# green.net
KiCad netlist of a schematic drawn in Altium Designer
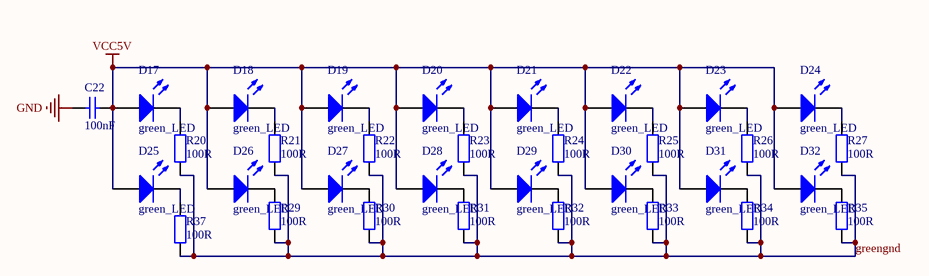
[diagram p0: green.SchDoc]

(export (version "E")
  (design (tool "Eeschema 10.0.6"))
  (components
    (comp (ref "C22")
      (value "100nF")
      (footprint "CC2012-0805")
      (description "Capacitor (Semiconductor SIM Model)")
      (fields (field (name "PUBLISHER") "Altium Limited"))
      (libsource (lib "Motorcontrol2.0") (part "Cap Semi"))
    )
    (comp (ref "D17")
      (value "green_LED")
      (footprint "LED5MM")
      (description "Typical RED GaAs LED")
      (fields (field (name "PUBLISHER") "Altium Limited"))
      (libsource (lib "Robocon_BJT") (part "LED"))
    )
    (comp (ref "D18")
      (value "green_LED")
      (footprint "LED5MM")
      (description "Typical RED GaAs LED")
      (fields (field (name "PUBLISHER") "Altium Limited"))
      (libsource (lib "Robocon_BJT") (part "LED"))
    )
    (comp (ref "D19")
      (value "green_LED")
      (footprint "LED5MM")
      (description "Typical RED GaAs LED")
      (fields (field (name "PUBLISHER") "Altium Limited"))
      (libsource (lib "Robocon_BJT") (part "LED"))
    )
    (comp (ref "D20")
      (value "green_LED")
      (footprint "LED5MM")
      (description "Typical RED GaAs LED")
      (fields (field (name "PUBLISHER") "Altium Limited"))
      (libsource (lib "Robocon_BJT") (part "LED"))
    )
    (comp (ref "D21")
      (value "green_LED")
      (footprint "LED5MM")
      (description "Typical RED GaAs LED")
      (fields (field (name "PUBLISHER") "Altium Limited"))
      (libsource (lib "Robocon_BJT") (part "LED"))
    )
    (comp (ref "D22")
      (value "green_LED")
      (footprint "LED5MM")
      (description "Typical RED GaAs LED")
      (fields (field (name "PUBLISHER") "Altium Limited"))
      (libsource (lib "Robocon_BJT") (part "LED"))
    )
    (comp (ref "D23")
      (value "green_LED")
      (footprint "LED5MM")
      (description "Typical RED GaAs LED")
      (fields (field (name "PUBLISHER") "Altium Limited"))
      (libsource (lib "Robocon_BJT") (part "LED"))
    )
    (comp (ref "D24")
      (value "green_LED")
      (footprint "LED5MM")
      (description "Typical RED GaAs LED")
      (fields (field (name "PUBLISHER") "Altium Limited"))
      (libsource (lib "Robocon_BJT") (part "LED"))
    )
    (comp (ref "D25")
      (value "green_LED")
      (footprint "LED5MM")
      (description "Typical RED GaAs LED")
      (fields (field (name "PUBLISHER") "Altium Limited"))
      (libsource (lib "Robocon_BJT") (part "LED"))
    )
    (comp (ref "D26")
      (value "green_LED")
      (footprint "LED5MM")
      (description "Typical RED GaAs LED")
      (fields (field (name "PUBLISHER") "Altium Limited"))
      (libsource (lib "Robocon_BJT") (part "LED"))
    )
    (comp (ref "D27")
      (value "green_LED")
      (footprint "LED5MM")
      (description "Typical RED GaAs LED")
      (fields (field (name "PUBLISHER") "Altium Limited"))
      (libsource (lib "Robocon_BJT") (part "LED"))
    )
    (comp (ref "D28")
      (value "green_LED")
      (footprint "LED5MM")
      (description "Typical RED GaAs LED")
      (fields (field (name "PUBLISHER") "Altium Limited"))
      (libsource (lib "Robocon_BJT") (part "LED"))
    )
    (comp (ref "D29")
      (value "green_LED")
      (footprint "LED5MM")
      (description "Typical RED GaAs LED")
      (fields (field (name "PUBLISHER") "Altium Limited"))
      (libsource (lib "Robocon_BJT") (part "LED"))
    )
    (comp (ref "D30")
      (value "green_LED")
      (footprint "LED5MM")
      (description "Typical RED GaAs LED")
      (fields (field (name "PUBLISHER") "Altium Limited"))
      (libsource (lib "Robocon_BJT") (part "LED"))
    )
    (comp (ref "D31")
      (value "green_LED")
      (footprint "LED5MM")
      (description "Typical RED GaAs LED")
      (fields (field (name "PUBLISHER") "Altium Limited"))
      (libsource (lib "Robocon_BJT") (part "LED"))
    )
    (comp (ref "D32")
      (value "green_LED")
      (footprint "LED5MM")
      (description "Typical RED GaAs LED")
      (fields (field (name "PUBLISHER") "Altium Limited"))
      (libsource (lib "Robocon_BJT") (part "LED"))
    )
    (comp (ref "R20")
      (value "100R")
      (footprint "CR2012-0805")
      (description "Resistor")
      (fields (field (name "PUBLISHER") "Altium Limited"))
      (libsource (lib "Robocon_RCL") (part "Res2"))
    )
    (comp (ref "R21")
      (value "100R")
      (footprint "CR2012-0805")
      (description "Resistor")
      (fields (field (name "PUBLISHER") "Altium Limited"))
      (libsource (lib "Robocon_RCL") (part "Res2"))
    )
    (comp (ref "R22")
      (value "100R")
      (footprint "CR2012-0805")
      (description "Resistor")
      (fields (field (name "PUBLISHER") "Altium Limited"))
      (libsource (lib "Robocon_RCL") (part "Res2"))
    )
    (comp (ref "R23")
      (value "100R")
      (footprint "CR2012-0805")
      (description "Resistor")
      (fields (field (name "PUBLISHER") "Altium Limited"))
      (libsource (lib "Robocon_RCL") (part "Res2"))
    )
    (comp (ref "R24")
      (value "100R")
      (footprint "CR2012-0805")
      (description "Resistor")
      (fields (field (name "PUBLISHER") "Altium Limited"))
      (libsource (lib "Robocon_RCL") (part "Res2"))
    )
    (comp (ref "R25")
      (value "100R")
      (footprint "CR2012-0805")
      (description "Resistor")
      (fields (field (name "PUBLISHER") "Altium Limited"))
      (libsource (lib "Robocon_RCL") (part "Res2"))
    )
    (comp (ref "R26")
      (value "100R")
      (footprint "CR2012-0805")
      (description "Resistor")
      (fields (field (name "PUBLISHER") "Altium Limited"))
      (libsource (lib "Robocon_RCL") (part "Res2"))
    )
    (comp (ref "R27")
      (value "100R")
      (footprint "CR2012-0805")
      (description "Resistor")
      (fields (field (name "PUBLISHER") "Altium Limited"))
      (libsource (lib "Robocon_RCL") (part "Res2"))
    )
    (comp (ref "R29")
      (value "100R")
      (footprint "CR2012-0805")
      (description "Resistor")
      (fields (field (name "PUBLISHER") "Altium Limited"))
      (libsource (lib "Robocon_RCL") (part "Res2"))
    )
    (comp (ref "R30")
      (value "100R")
      (footprint "CR2012-0805")
      (description "Resistor")
      (fields (field (name "PUBLISHER") "Altium Limited"))
      (libsource (lib "Robocon_RCL") (part "Res2"))
    )
    (comp (ref "R31")
      (value "100R")
      (footprint "CR2012-0805")
      (description "Resistor")
      (fields (field (name "PUBLISHER") "Altium Limited"))
      (libsource (lib "Robocon_RCL") (part "Res2"))
    )
    (comp (ref "R32")
      (value "100R")
      (footprint "CR2012-0805")
      (description "Resistor")
      (fields (field (name "PUBLISHER") "Altium Limited"))
      (libsource (lib "Robocon_RCL") (part "Res2"))
    )
    (comp (ref "R33")
      (value "100R")
      (footprint "CR2012-0805")
      (description "Resistor")
      (fields (field (name "PUBLISHER") "Altium Limited"))
      (libsource (lib "Robocon_RCL") (part "Res2"))
    )
    (comp (ref "R34")
      (value "100R")
      (footprint "CR2012-0805")
      (description "Resistor")
      (fields (field (name "PUBLISHER") "Altium Limited"))
      (libsource (lib "Robocon_RCL") (part "Res2"))
    )
    (comp (ref "R35")
      (value "100R")
      (footprint "CR2012-0805")
      (description "Resistor")
      (fields (field (name "PUBLISHER") "Altium Limited"))
      (libsource (lib "Robocon_RCL") (part "Res2"))
    )
    (comp (ref "R37")
      (value "100R")
      (footprint "CR2012-0805")
      (description "Resistor")
      (fields (field (name "PUBLISHER") "Altium Limited"))
      (libsource (lib "Robocon_RCL") (part "Res2"))
    )
  )
  (nets
    (net (code "1") (name "/greengnd") (class "Default")
      (node (ref "R20") (pin "1") (pinfunction "1_1") (pintype "passive"))
      (node (ref "R21") (pin "1") (pinfunction "1_1") (pintype "passive"))
      (node (ref "R22") (pin "1") (pinfunction "1_1") (pintype "passive"))
      (node (ref "R23") (pin "1") (pinfunction "1_1") (pintype "passive"))
      (node (ref "R24") (pin "1") (pinfunction "1_1") (pintype "passive"))
      (node (ref "R25") (pin "1") (pinfunction "1_1") (pintype "passive"))
      (node (ref "R26") (pin "1") (pinfunction "1_1") (pintype "passive"))
      (node (ref "R27") (pin "1") (pinfunction "1_1") (pintype "passive"))
      (node (ref "R29") (pin "1") (pinfunction "1_1") (pintype "passive"))
      (node (ref "R30") (pin "1") (pinfunction "1_1") (pintype "passive"))
      (node (ref "R31") (pin "1") (pinfunction "1_1") (pintype "passive"))
      (node (ref "R32") (pin "1") (pinfunction "1_1") (pintype "passive"))
      (node (ref "R33") (pin "1") (pinfunction "1_1") (pintype "passive"))
      (node (ref "R34") (pin "1") (pinfunction "1_1") (pintype "passive"))
      (node (ref "R35") (pin "1") (pinfunction "1_1") (pintype "passive"))
      (node (ref "R37") (pin "1") (pinfunction "1_1") (pintype "passive"))
    )
    (net (code "2") (name "GND") (class "Default")
      (node (ref "C22") (pin "2") (pinfunction "2_2") (pintype "passive"))
    )
    (net (code "3") (name "Net-(D17-K)") (class "Default")
      (node (ref "D17") (pin "2") (pinfunction "K_2") (pintype "passive"))
      (node (ref "R20") (pin "2") (pinfunction "2_2") (pintype "passive"))
    )
    (net (code "4") (name "Net-(D18-K)") (class "Default")
      (node (ref "D18") (pin "2") (pinfunction "K_2") (pintype "passive"))
      (node (ref "R21") (pin "2") (pinfunction "2_2") (pintype "passive"))
    )
    (net (code "5") (name "Net-(D19-K)") (class "Default")
      (node (ref "D19") (pin "2") (pinfunction "K_2") (pintype "passive"))
      (node (ref "R22") (pin "2") (pinfunction "2_2") (pintype "passive"))
    )
    (net (code "6") (name "Net-(D20-K)") (class "Default")
      (node (ref "D20") (pin "2") (pinfunction "K_2") (pintype "passive"))
      (node (ref "R23") (pin "2") (pinfunction "2_2") (pintype "passive"))
    )
    (net (code "7") (name "Net-(D21-K)") (class "Default")
      (node (ref "D21") (pin "2") (pinfunction "K_2") (pintype "passive"))
      (node (ref "R24") (pin "2") (pinfunction "2_2") (pintype "passive"))
    )
    (net (code "8") (name "Net-(D22-K)") (class "Default")
      (node (ref "D22") (pin "2") (pinfunction "K_2") (pintype "passive"))
      (node (ref "R25") (pin "2") (pinfunction "2_2") (pintype "passive"))
    )
    (net (code "9") (name "Net-(D23-K)") (class "Default")
      (node (ref "D23") (pin "2") (pinfunction "K_2") (pintype "passive"))
      (node (ref "R26") (pin "2") (pinfunction "2_2") (pintype "passive"))
    )
    (net (code "10") (name "Net-(D24-K)") (class "Default")
      (node (ref "D24") (pin "2") (pinfunction "K_2") (pintype "passive"))
      (node (ref "R27") (pin "2") (pinfunction "2_2") (pintype "passive"))
    )
    (net (code "11") (name "Net-(D25-K)") (class "Default")
      (node (ref "D25") (pin "2") (pinfunction "K_2") (pintype "passive"))
      (node (ref "R37") (pin "2") (pinfunction "2_2") (pintype "passive"))
    )
    (net (code "12") (name "Net-(D26-K)") (class "Default")
      (node (ref "D26") (pin "2") (pinfunction "K_2") (pintype "passive"))
      (node (ref "R29") (pin "2") (pinfunction "2_2") (pintype "passive"))
    )
    (net (code "13") (name "Net-(D27-K)") (class "Default")
      (node (ref "D27") (pin "2") (pinfunction "K_2") (pintype "passive"))
      (node (ref "R30") (pin "2") (pinfunction "2_2") (pintype "passive"))
    )
    (net (code "14") (name "Net-(D28-K)") (class "Default")
      (node (ref "D28") (pin "2") (pinfunction "K_2") (pintype "passive"))
      (node (ref "R31") (pin "2") (pinfunction "2_2") (pintype "passive"))
    )
    (net (code "15") (name "Net-(D29-K)") (class "Default")
      (node (ref "D29") (pin "2") (pinfunction "K_2") (pintype "passive"))
      (node (ref "R32") (pin "2") (pinfunction "2_2") (pintype "passive"))
    )
    (net (code "16") (name "Net-(D30-K)") (class "Default")
      (node (ref "D30") (pin "2") (pinfunction "K_2") (pintype "passive"))
      (node (ref "R33") (pin "2") (pinfunction "2_2") (pintype "passive"))
    )
    (net (code "17") (name "Net-(D31-K)") (class "Default")
      (node (ref "D31") (pin "2") (pinfunction "K_2") (pintype "passive"))
      (node (ref "R34") (pin "2") (pinfunction "2_2") (pintype "passive"))
    )
    (net (code "18") (name "Net-(D32-K)") (class "Default")
      (node (ref "D32") (pin "2") (pinfunction "K_2") (pintype "passive"))
      (node (ref "R35") (pin "2") (pinfunction "2_2") (pintype "passive"))
    )
    (net (code "19") (name "VCC5V") (class "Default")
      (node (ref "C22") (pin "1") (pinfunction "1_1") (pintype "passive"))
      (node (ref "D17") (pin "1") (pinfunction "A_1") (pintype "passive"))
      (node (ref "D18") (pin "1") (pinfunction "A_1") (pintype "passive"))
      (node (ref "D19") (pin "1") (pinfunction "A_1") (pintype "passive"))
      (node (ref "D20") (pin "1") (pinfunction "A_1") (pintype "passive"))
      (node (ref "D21") (pin "1") (pinfunction "A_1") (pintype "passive"))
      (node (ref "D22") (pin "1") (pinfunction "A_1") (pintype "passive"))
      (node (ref "D23") (pin "1") (pinfunction "A_1") (pintype "passive"))
      (node (ref "D24") (pin "1") (pinfunction "A_1") (pintype "passive"))
      (node (ref "D25") (pin "1") (pinfunction "A_1") (pintype "passive"))
      (node (ref "D26") (pin "1") (pinfunction "A_1") (pintype "passive"))
      (node (ref "D27") (pin "1") (pinfunction "A_1") (pintype "passive"))
      (node (ref "D28") (pin "1") (pinfunction "A_1") (pintype "passive"))
      (node (ref "D29") (pin "1") (pinfunction "A_1") (pintype "passive"))
      (node (ref "D30") (pin "1") (pinfunction "A_1") (pintype "passive"))
      (node (ref "D31") (pin "1") (pinfunction "A_1") (pintype "passive"))
      (node (ref "D32") (pin "1") (pinfunction "A_1") (pintype "passive"))
    )
  )
)
